# A_Flotador.net
KiCad netlist of a schematic drawn in Altium Designer
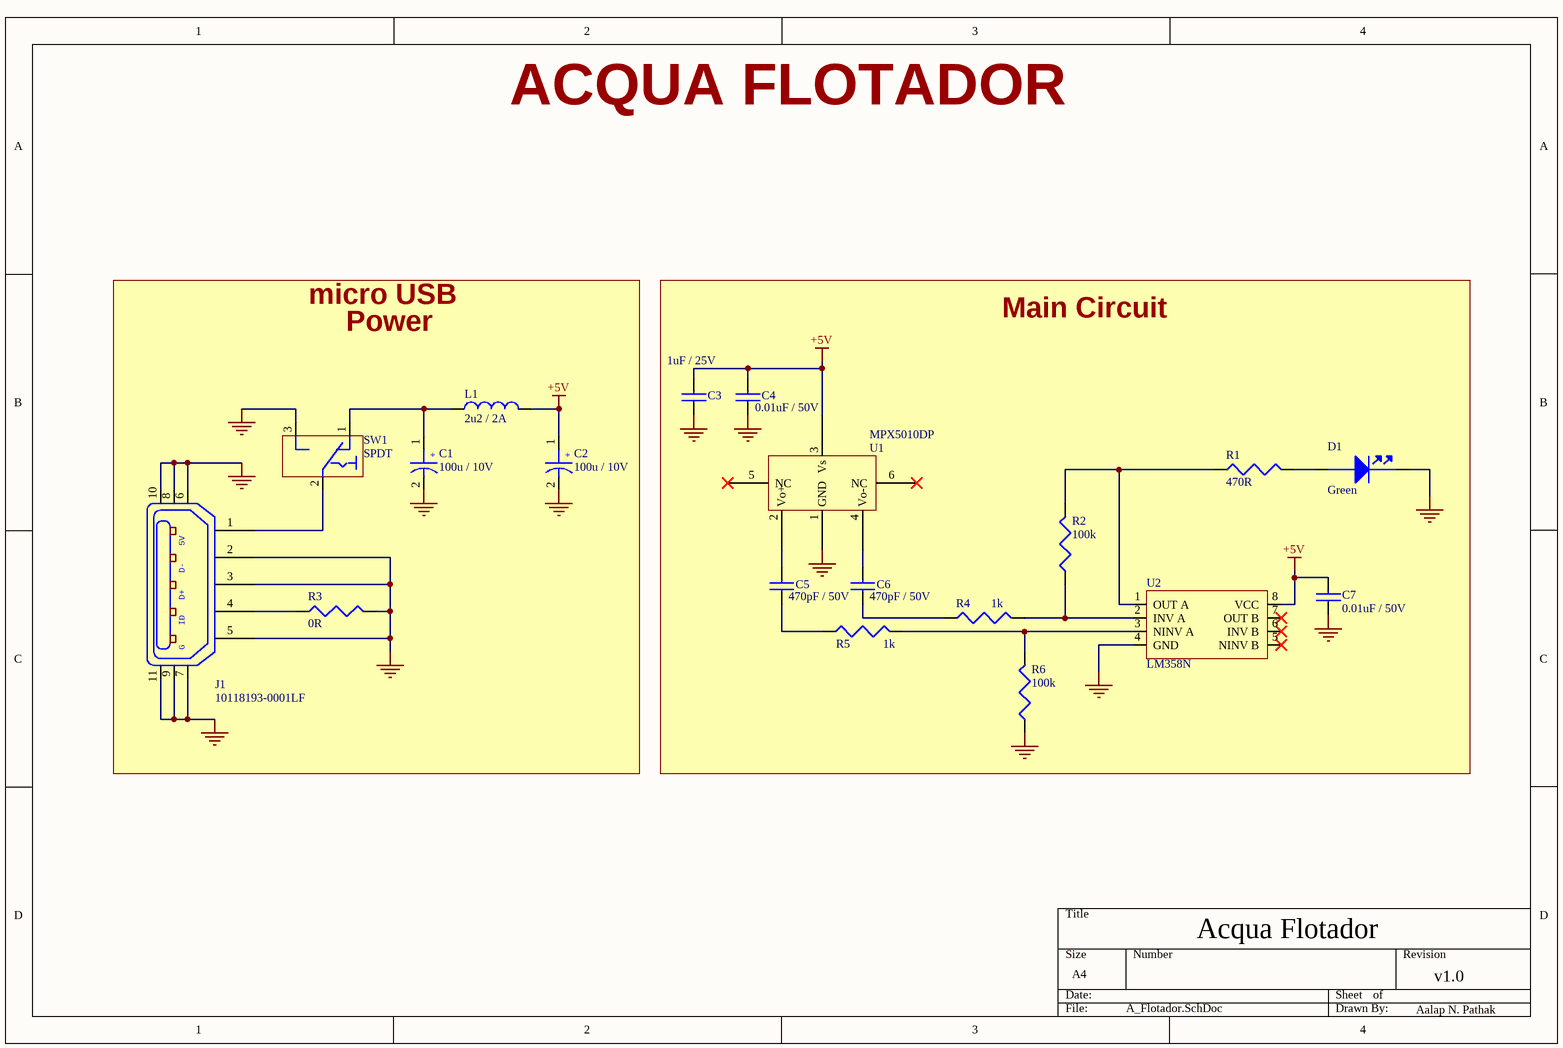
[diagram p0: A_Flotador.SchDoc]

(export (version "E")
  (design (tool "Eeschema 10.0.6"))
  (components
    (comp (ref "C1")
      (value "100u / 10V")
      (footprint "C_ALU_C_SIZE")
      (description "Cap Aluminum 100uF 10V 20% (5 X 5.4mm) SMD 50mA 1000 hr 85°C T/R")
      (fields
        (field (name "MANUFACTURER") "Panasonic")
        (field (name "MANUFACTURER PART NUMBER") "EEE-1AA101WR")
      )
      (libsource (lib "AFlotador_SchLib") (part "EEE-1AA101WR"))
    )
    (comp (ref "C2")
      (value "100u / 10V")
      (footprint "C_ALU_C_SIZE")
      (description "Cap Aluminum 100uF 10V 20% (5 X 5.4mm) SMD 50mA 1000 hr 85°C T/R")
      (fields
        (field (name "MANUFACTURER") "Panasonic")
        (field (name "MANUFACTURER PART NUMBER") "EEE-1AA101WR")
      )
      (libsource (lib "AFlotador_SchLib") (part "EEE-1AA101WR"))
    )
    (comp (ref "C3")
      (value "1uF / 25V")
      (footprint "C0805")
      (description "CAP CER 1UF 25V X5R 0805")
      (fields
        (field (name "MANUFACTURER") "TDK")
        (field (name "MANUFACTURER PART NUMBER") "C2012X5R1E105K125AA")
      )
      (libsource (lib "AFlotador_SchLib") (part "C2012X5R1E105K125AA"))
    )
    (comp (ref "C4")
      (value "0.01uF / 50V")
      (footprint "C0805")
      (description "CAP CER 0.01UF 50V X7R 0805")
      (fields
        (field (name "MANUFACTURER") "KEMET")
        (field (name "MANUFACTURER PART NUMBER") "C0805C103K5RACTU")
      )
      (libsource (lib "AFlotador_SchLib") (part "C0805C103K5RACTU"))
    )
    (comp (ref "C5")
      (value "470pF / 50V")
      (footprint "C0805")
      (description "CAP CER 470PF 50V X7R 0805")
      (fields
        (field (name "MANUFACTURER") "KEMET")
        (field (name "MANUFACTURER PART NUMBER") "C0805C471K5RACTU")
      )
      (libsource (lib "AFlotador_SchLib") (part "C0805C471K5RACTU"))
    )
    (comp (ref "C6")
      (value "470pF / 50V")
      (footprint "C0805")
      (description "CAP CER 470PF 50V X7R 0805")
      (fields
        (field (name "MANUFACTURER") "KEMET")
        (field (name "MANUFACTURER PART NUMBER") "C0805C471K5RACTU")
      )
      (libsource (lib "AFlotador_SchLib") (part "C0805C471K5RACTU"))
    )
    (comp (ref "C7")
      (value "0.01uF / 50V")
      (footprint "C0805")
      (description "CAP CER 0.01UF 50V X7R 0805")
      (fields
        (field (name "MANUFACTURER") "KEMET")
        (field (name "MANUFACTURER PART NUMBER") "C0805C103K5RACTU")
      )
      (libsource (lib "AFlotador_SchLib") (part "C0805C103K5RACTU"))
    )
    (comp (ref "D1")
      (value "Green")
      (footprint "LED_0603")
      (description "LED Uni-Color Green 572nm 2-Pin Chip 0603(1608Metric) T/R")
      (fields
        (field (name "MANUFACTURER") "Osram Opto")
        (field (name "MANUFACTURER PART NUMBER") "LGL29K-G2J1-24-Z")
      )
      (libsource (lib "AFlotador_SchLib") (part "LGL29K-G2J1-24-Z"))
    )
    (comp (ref "J1")
      (value "10118193-0001LF")
      (footprint "MicroUSB")
      (description "CONN RCPT USB2.0 MICRO B SMD R/A")
      (fields (field (name "MANUFACTURER") "Amphenol FCI"))
      (libsource (lib "AFlotador_SchLib") (part "10118193-0001LF"))
    )
    (comp (ref "L1")
      (value "2u2 / 2A")
      (footprint "C1210_IND")
      (description "FIXED IND 2.2UH 2A 80 MOHM SMD")
      (fields
        (field (name "MANUFACTURER") "KEMET")
        (field (name "MANUFACTURER PART NUMBER") "L1210R2R2MDWIT")
      )
      (libsource (lib "AFlotador_SchLib") (part "L1210R2R2MDWIT"))
    )
    (comp (ref "R1")
      (value "470R")
      (footprint "R0805")
      (description "RES SMD 470 OHM 1% 1/8W 0805")
      (fields
        (field (name "MANUFACTURER") "Yageo")
        (field (name "MANUFACTURER PART NUMBER") "RC0805FR-07470RL")
      )
      (libsource (lib "AFlotador_SchLib") (part "RC0805FR-07470RL"))
    )
    (comp (ref "R2")
      (value "100k")
      (footprint "R0805")
      (description "RES SMD 100K OHM 1% 1/8W 0805")
      (fields
        (field (name "MANUFACTURER") "Yageo")
        (field (name "MANUFACTURER PART NUMBER") "RC0805FR-07100KL")
      )
      (libsource (lib "AFlotador_SchLib") (part "RC0805FR-07100KL"))
    )
    (comp (ref "R3")
      (value "0R")
      (footprint "R0805")
      (description "RES SMD 0 OHM JUMPER 1/8W 0805")
      (fields
        (field (name "MANUFACTURER") "Yageo")
        (field (name "MANUFACTURER PART NUMBER") "RC0805JR-070RL")
      )
      (libsource (lib "AFlotador_SchLib") (part "RC0805JR-070RL"))
    )
    (comp (ref "R4")
      (value "1k")
      (footprint "R0805")
      (description "RES SMD 1K OHM 1% 1/8W 0805")
      (fields
        (field (name "MANUFACTURER") "Yageo Phycomp")
        (field (name "MANUFACTURER PART NUMBER") "RC0805FR-071KL")
      )
      (libsource (lib "AFlotador_SchLib") (part "RC0805FR-071KL"))
    )
    (comp (ref "R5")
      (value "1k")
      (footprint "R0805")
      (description "RES SMD 1K OHM 1% 1/8W 0805")
      (fields
        (field (name "MANUFACTURER") "Yageo Phycomp")
        (field (name "MANUFACTURER PART NUMBER") "RC0805FR-071KL")
      )
      (libsource (lib "AFlotador_SchLib") (part "RC0805FR-071KL"))
    )
    (comp (ref "R6")
      (value "100k")
      (footprint "R0805")
      (description "RES SMD 100K OHM 1% 1/8W 0805")
      (fields
        (field (name "MANUFACTURER") "Yageo")
        (field (name "MANUFACTURER PART NUMBER") "RC0805FR-07100KL")
      )
      (libsource (lib "AFlotador_SchLib") (part "RC0805FR-07100KL"))
    )
    (comp (ref "SW1")
      (value "SPDT")
      (footprint "SPDT")
      (fields
        (field (name "MANUFACTURER") "ITT C&K")
        (field (name "MANUFACTURER PART NUMBER") "OS102011MS2QN1")
      )
      (libsource (lib "AFlotador_SchLib") (part "OS102011MS2QN1"))
    )
    (comp (ref "U1")
      (value "MPX5010DP")
      (footprint "MPX5010DP")
      (fields (field (name "MANUFACTURER") "NXP Freescale"))
      (libsource (lib "AFlotador_SchLib") (part "MPX5010DP"))
    )
    (comp (ref "U2")
      (value "LM358N")
      (footprint "LM358N")
      (description "IC OPAMP GP 1MHZ 8DIP")
      (fields
        (field (name "MANUFACTURER") "TI National Semiconductor")
        (field (name "MANUFACTURER PART NUMBER") "LM358N/NOPB")
      )
      (libsource (lib "AFlotador_SchLib") (part "LM358N/NOPB"))
    )
  )
  (nets
    (net (code "1") (name "+5V") (class "Default")
      (node (ref "C2") (pin "1") (pinfunction "1_1") (pintype "passive"))
      (node (ref "C3") (pin "2") (pinfunction "2_2") (pintype "passive"))
      (node (ref "C4") (pin "2") (pinfunction "2_2") (pintype "passive"))
      (node (ref "C7") (pin "2") (pinfunction "2_2") (pintype "passive"))
      (node (ref "L1") (pin "2") (pinfunction "2_2") (pintype "passive"))
      (node (ref "U1") (pin "3") (pinfunction "Vs_3") (pintype "passive"))
      (node (ref "U2") (pin "8") (pinfunction "VCC_8") (pintype "passive"))
    )
    (net (code "2") (name "GND") (class "Default")
      (node (ref "C1") (pin "2") (pinfunction "2_2") (pintype "passive"))
      (node (ref "C2") (pin "2") (pinfunction "2_2") (pintype "passive"))
      (node (ref "C3") (pin "1") (pinfunction "1_1") (pintype "passive"))
      (node (ref "C4") (pin "1") (pinfunction "1_1") (pintype "passive"))
      (node (ref "C7") (pin "1") (pinfunction "1_1") (pintype "passive"))
      (node (ref "D1") (pin "1") (pinfunction "Cathode_1") (pintype "passive"))
      (node (ref "J1") (pin "10") (pinfunction "10_10") (pintype "passive"))
      (node (ref "J1") (pin "11") (pinfunction "11_11") (pintype "passive"))
      (node (ref "J1") (pin "2") (pinfunction "2_2") (pintype "passive"))
      (node (ref "J1") (pin "3") (pinfunction "3_3") (pintype "passive"))
      (node (ref "J1") (pin "5") (pinfunction "5_5") (pintype "passive"))
      (node (ref "J1") (pin "6") (pinfunction "6_6") (pintype "passive"))
      (node (ref "J1") (pin "7") (pinfunction "7_7") (pintype "passive"))
      (node (ref "J1") (pin "8") (pinfunction "8_8") (pintype "passive"))
      (node (ref "J1") (pin "9") (pinfunction "9_9") (pintype "passive"))
      (node (ref "R3") (pin "2") (pinfunction "2_2") (pintype "passive"))
      (node (ref "R6") (pin "1") (pinfunction "1_1") (pintype "passive"))
      (node (ref "SW1") (pin "3") (pinfunction "3_3") (pintype "passive"))
      (node (ref "U1") (pin "1") (pinfunction "GND_1") (pintype "passive"))
      (node (ref "U2") (pin "4") (pinfunction "GND_4") (pintype "passive"))
    )
    (net (code "3") (name "Net-(C1-Pad1)") (class "Default")
      (node (ref "C1") (pin "1") (pinfunction "1_1") (pintype "passive"))
      (node (ref "L1") (pin "1") (pinfunction "1_1") (pintype "passive"))
      (node (ref "SW1") (pin "1") (pinfunction "1_1") (pintype "passive"))
    )
    (net (code "4") (name "Net-(C5-Pad1)") (class "Default")
      (node (ref "C5") (pin "1") (pinfunction "1_1") (pintype "passive"))
      (node (ref "R5") (pin "1") (pinfunction "1_1") (pintype "passive"))
    )
    (net (code "5") (name "Net-(C6-Pad1)") (class "Default")
      (node (ref "C6") (pin "1") (pinfunction "1_1") (pintype "passive"))
      (node (ref "R4") (pin "1") (pinfunction "1_1") (pintype "passive"))
    )
    (net (code "6") (name "Net-(D1-Anode)") (class "Default")
      (node (ref "D1") (pin "2") (pinfunction "Anode_2") (pintype "passive"))
      (node (ref "R1") (pin "2") (pinfunction "2_2") (pintype "passive"))
    )
    (net (code "7") (name "Net-(J1-Pad1)") (class "Default")
      (node (ref "J1") (pin "1") (pinfunction "1_1") (pintype "passive"))
      (node (ref "SW1") (pin "2") (pinfunction "2_2") (pintype "passive"))
    )
    (net (code "8") (name "Net-(J1-Pad4)") (class "Default")
      (node (ref "J1") (pin "4") (pinfunction "4_4") (pintype "passive"))
      (node (ref "R3") (pin "1") (pinfunction "1_1") (pintype "passive"))
    )
    (net (code "9") (name "Net-(U1-Vo+)") (class "Default")
      (node (ref "C5") (pin "2") (pinfunction "2_2") (pintype "passive"))
      (node (ref "U1") (pin "2") (pinfunction "Vo+_2") (pintype "passive"))
    )
    (net (code "10") (name "Net-(U1-Vo-)") (class "Default")
      (node (ref "C6") (pin "2") (pinfunction "2_2") (pintype "passive"))
      (node (ref "U1") (pin "4") (pinfunction "Vo-_4") (pintype "passive"))
    )
    (net (code "11") (name "Net-(U2-INV_A)") (class "Default")
      (node (ref "R2") (pin "1") (pinfunction "1_1") (pintype "passive"))
      (node (ref "R4") (pin "2") (pinfunction "2_2") (pintype "passive"))
      (node (ref "U2") (pin "2") (pinfunction "INV_A_2") (pintype "passive"))
    )
    (net (code "12") (name "Net-(U2-NINV_A)") (class "Default")
      (node (ref "R5") (pin "2") (pinfunction "2_2") (pintype "passive"))
      (node (ref "R6") (pin "2") (pinfunction "2_2") (pintype "passive"))
      (node (ref "U2") (pin "3") (pinfunction "NINV_A_3") (pintype "passive"))
    )
    (net (code "13") (name "Net-(U2-OUT_A)") (class "Default")
      (node (ref "R1") (pin "1") (pinfunction "1_1") (pintype "passive"))
      (node (ref "R2") (pin "2") (pinfunction "2_2") (pintype "passive"))
      (node (ref "U2") (pin "1") (pinfunction "OUT_A_1") (pintype "passive"))
    )
    (net (code "14") (name "unconnected-(U1-NC-Pad5)") (class "Default")
      (node (ref "U1") (pin "5") (pinfunction "NC_5") (pintype "passive+no_connect"))
    )
    (net (code "15") (name "unconnected-(U1-NC-Pad6)") (class "Default")
      (node (ref "U1") (pin "6") (pinfunction "NC_6") (pintype "passive+no_connect"))
    )
    (net (code "16") (name "unconnected-(U2-INV_B-Pad6)") (class "Default")
      (node (ref "U2") (pin "6") (pinfunction "INV_B_6") (pintype "passive+no_connect"))
    )
    (net (code "17") (name "unconnected-(U2-NINV_B-Pad5)") (class "Default")
      (node (ref "U2") (pin "5") (pinfunction "NINV_B_5") (pintype "passive+no_connect"))
    )
    (net (code "18") (name "unconnected-(U2-OUT_B-Pad7)") (class "Default")
      (node (ref "U2") (pin "7") (pinfunction "OUT_B_7") (pintype "passive+no_connect"))
    )
  )
)
